# 2_matrix.net
KiCad netlist of a schematic drawn in Altium Designer
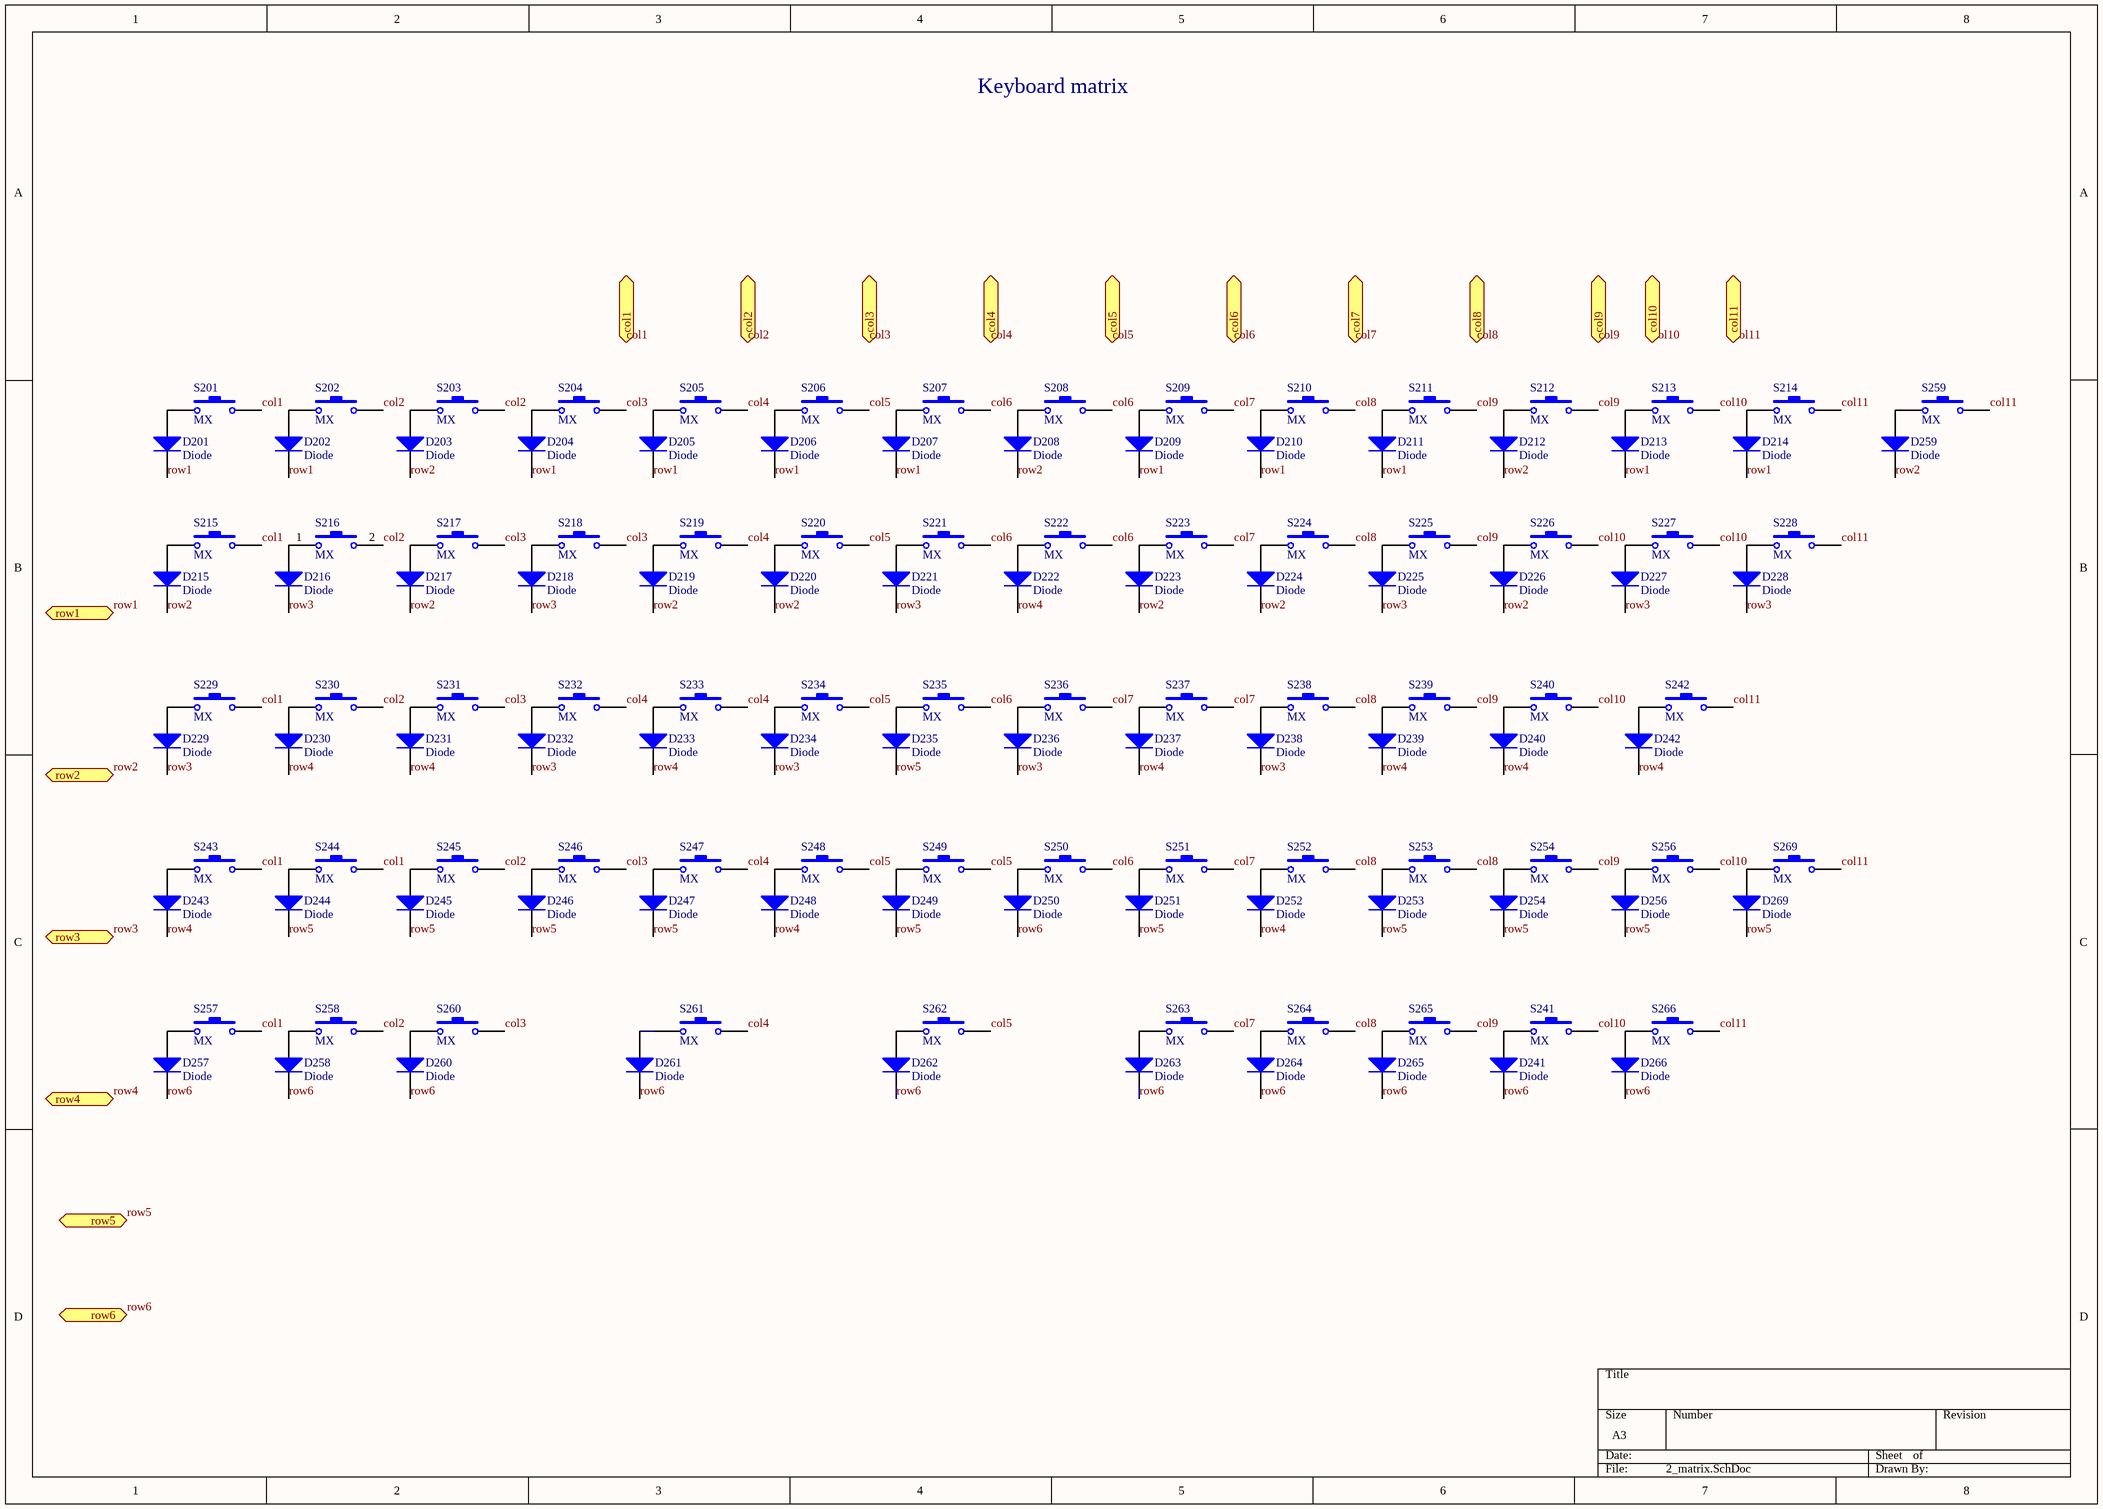
[diagram p0: 2_matrix.SchDoc]

(export (version "E")
  (design (tool "Eeschema 10.0.6"))
  (components
    (comp (ref "D201")
      (value "Diode")
      (footprint "D0603[1608]")
      (description "Default Diode")
      (fields (field (name "MFG") "Bourns Inc.") (field (name "MRF.PART") "CD4148WTP"))
      (libsource (lib "Miscellaneous Devices") (part "Diode"))
    )
    (comp (ref "D202")
      (value "Diode")
      (footprint "D0603[1608]")
      (description "Default Diode")
      (fields (field (name "MFG") "Bourns Inc.") (field (name "MRF.PART") "CD4148WTP"))
      (libsource (lib "Miscellaneous Devices") (part "Diode"))
    )
    (comp (ref "D203")
      (value "Diode")
      (footprint "D0603[1608]")
      (description "Default Diode")
      (fields (field (name "MFG") "Bourns Inc.") (field (name "MRF.PART") "CD4148WTP"))
      (libsource (lib "Miscellaneous Devices") (part "Diode"))
    )
    (comp (ref "D204")
      (value "Diode")
      (footprint "D0603[1608]")
      (description "Default Diode")
      (fields (field (name "MFG") "Bourns Inc.") (field (name "MRF.PART") "CD4148WTP"))
      (libsource (lib "Miscellaneous Devices") (part "Diode"))
    )
    (comp (ref "D205")
      (value "Diode")
      (footprint "D0603[1608]")
      (description "Default Diode")
      (fields (field (name "MFG") "Bourns Inc.") (field (name "MRF.PART") "CD4148WTP"))
      (libsource (lib "Miscellaneous Devices") (part "Diode"))
    )
    (comp (ref "D206")
      (value "Diode")
      (footprint "D0603[1608]")
      (description "Default Diode")
      (fields (field (name "MFG") "Bourns Inc.") (field (name "MRF.PART") "CD4148WTP"))
      (libsource (lib "Miscellaneous Devices") (part "Diode"))
    )
    (comp (ref "D207")
      (value "Diode")
      (footprint "D0603[1608]")
      (description "Default Diode")
      (fields (field (name "MFG") "Bourns Inc.") (field (name "MRF.PART") "CD4148WTP"))
      (libsource (lib "Miscellaneous Devices") (part "Diode"))
    )
    (comp (ref "D208")
      (value "Diode")
      (footprint "D0603[1608]")
      (description "Default Diode")
      (fields (field (name "MFG") "Bourns Inc.") (field (name "MRF.PART") "CD4148WTP"))
      (libsource (lib "Miscellaneous Devices") (part "Diode"))
    )
    (comp (ref "D209")
      (value "Diode")
      (footprint "D0603[1608]")
      (description "Default Diode")
      (fields (field (name "MFG") "Bourns Inc.") (field (name "MRF.PART") "CD4148WTP"))
      (libsource (lib "Miscellaneous Devices") (part "Diode"))
    )
    (comp (ref "D210")
      (value "Diode")
      (footprint "D0603[1608]")
      (description "Default Diode")
      (fields (field (name "MFG") "Bourns Inc.") (field (name "MRF.PART") "CD4148WTP"))
      (libsource (lib "Miscellaneous Devices") (part "Diode"))
    )
    (comp (ref "D211")
      (value "Diode")
      (footprint "D0603[1608]")
      (description "Default Diode")
      (fields (field (name "MFG") "Bourns Inc.") (field (name "MRF.PART") "CD4148WTP"))
      (libsource (lib "Miscellaneous Devices") (part "Diode"))
    )
    (comp (ref "D212")
      (value "Diode")
      (footprint "D0603[1608]")
      (description "Default Diode")
      (fields (field (name "MFG") "Bourns Inc.") (field (name "MRF.PART") "CD4148WTP"))
      (libsource (lib "Miscellaneous Devices") (part "Diode"))
    )
    (comp (ref "D213")
      (value "Diode")
      (footprint "D0603[1608]")
      (description "Default Diode")
      (fields (field (name "MFG") "Bourns Inc.") (field (name "MRF.PART") "CD4148WTP"))
      (libsource (lib "Miscellaneous Devices") (part "Diode"))
    )
    (comp (ref "D214")
      (value "Diode")
      (footprint "D0603[1608]")
      (description "Default Diode")
      (fields (field (name "MFG") "Bourns Inc.") (field (name "MRF.PART") "CD4148WTP"))
      (libsource (lib "Miscellaneous Devices") (part "Diode"))
    )
    (comp (ref "D215")
      (value "Diode")
      (footprint "D0603[1608]")
      (description "Default Diode")
      (fields (field (name "MFG") "Bourns Inc.") (field (name "MRF.PART") "CD4148WTP"))
      (libsource (lib "Miscellaneous Devices") (part "Diode"))
    )
    (comp (ref "D216")
      (value "Diode")
      (footprint "D0603[1608]")
      (description "Default Diode")
      (fields (field (name "MFG") "Bourns Inc.") (field (name "MRF.PART") "CD4148WTP"))
      (libsource (lib "Miscellaneous Devices") (part "Diode"))
    )
    (comp (ref "D217")
      (value "Diode")
      (footprint "D0603[1608]")
      (description "Default Diode")
      (fields (field (name "MFG") "Bourns Inc.") (field (name "MRF.PART") "CD4148WTP"))
      (libsource (lib "Miscellaneous Devices") (part "Diode"))
    )
    (comp (ref "D218")
      (value "Diode")
      (footprint "D0603[1608]")
      (description "Default Diode")
      (fields (field (name "MFG") "Bourns Inc.") (field (name "MRF.PART") "CD4148WTP"))
      (libsource (lib "Miscellaneous Devices") (part "Diode"))
    )
    (comp (ref "D219")
      (value "Diode")
      (footprint "D0603[1608]")
      (description "Default Diode")
      (fields (field (name "MFG") "Bourns Inc.") (field (name "MRF.PART") "CD4148WTP"))
      (libsource (lib "Miscellaneous Devices") (part "Diode"))
    )
    (comp (ref "D220")
      (value "Diode")
      (footprint "D0603[1608]")
      (description "Default Diode")
      (fields (field (name "MFG") "Bourns Inc.") (field (name "MRF.PART") "CD4148WTP"))
      (libsource (lib "Miscellaneous Devices") (part "Diode"))
    )
    (comp (ref "D221")
      (value "Diode")
      (footprint "D0603[1608]")
      (description "Default Diode")
      (fields (field (name "MFG") "Bourns Inc.") (field (name "MRF.PART") "CD4148WTP"))
      (libsource (lib "Miscellaneous Devices") (part "Diode"))
    )
    (comp (ref "D222")
      (value "Diode")
      (footprint "D0603[1608]")
      (description "Default Diode")
      (fields (field (name "MFG") "Bourns Inc.") (field (name "MRF.PART") "CD4148WTP"))
      (libsource (lib "Miscellaneous Devices") (part "Diode"))
    )
    (comp (ref "D223")
      (value "Diode")
      (footprint "D0603[1608]")
      (description "Default Diode")
      (fields (field (name "MFG") "Bourns Inc.") (field (name "MRF.PART") "CD4148WTP"))
      (libsource (lib "Miscellaneous Devices") (part "Diode"))
    )
    (comp (ref "D224")
      (value "Diode")
      (footprint "D0603[1608]")
      (description "Default Diode")
      (fields (field (name "MFG") "Bourns Inc.") (field (name "MRF.PART") "CD4148WTP"))
      (libsource (lib "Miscellaneous Devices") (part "Diode"))
    )
    (comp (ref "D225")
      (value "Diode")
      (footprint "D0603[1608]")
      (description "Default Diode")
      (fields (field (name "MFG") "Bourns Inc.") (field (name "MRF.PART") "CD4148WTP"))
      (libsource (lib "Miscellaneous Devices") (part "Diode"))
    )
    (comp (ref "D226")
      (value "Diode")
      (footprint "D0603[1608]")
      (description "Default Diode")
      (fields (field (name "MFG") "Bourns Inc.") (field (name "MRF.PART") "CD4148WTP"))
      (libsource (lib "Miscellaneous Devices") (part "Diode"))
    )
    (comp (ref "D227")
      (value "Diode")
      (footprint "D0603[1608]")
      (description "Default Diode")
      (fields (field (name "MFG") "Bourns Inc.") (field (name "MRF.PART") "CD4148WTP"))
      (libsource (lib "Miscellaneous Devices") (part "Diode"))
    )
    (comp (ref "D228")
      (value "Diode")
      (footprint "D0603[1608]")
      (description "Default Diode")
      (fields (field (name "MFG") "Bourns Inc.") (field (name "MRF.PART") "CD4148WTP"))
      (libsource (lib "Miscellaneous Devices") (part "Diode"))
    )
    (comp (ref "D229")
      (value "Diode")
      (footprint "D0603[1608]")
      (description "Default Diode")
      (fields (field (name "MFG") "Bourns Inc.") (field (name "MRF.PART") "CD4148WTP"))
      (libsource (lib "Miscellaneous Devices") (part "Diode"))
    )
    (comp (ref "D230")
      (value "Diode")
      (footprint "D0603[1608]")
      (description "Default Diode")
      (fields (field (name "MFG") "Bourns Inc.") (field (name "MRF.PART") "CD4148WTP"))
      (libsource (lib "Miscellaneous Devices") (part "Diode"))
    )
    (comp (ref "D231")
      (value "Diode")
      (footprint "D0603[1608]")
      (description "Default Diode")
      (fields (field (name "MFG") "Bourns Inc.") (field (name "MRF.PART") "CD4148WTP"))
      (libsource (lib "Miscellaneous Devices") (part "Diode"))
    )
    (comp (ref "D232")
      (value "Diode")
      (footprint "D0603[1608]")
      (description "Default Diode")
      (fields (field (name "MFG") "Bourns Inc.") (field (name "MRF.PART") "CD4148WTP"))
      (libsource (lib "Miscellaneous Devices") (part "Diode"))
    )
    (comp (ref "D233")
      (value "Diode")
      (footprint "D0603[1608]")
      (description "Default Diode")
      (fields (field (name "MFG") "Bourns Inc.") (field (name "MRF.PART") "CD4148WTP"))
      (libsource (lib "Miscellaneous Devices") (part "Diode"))
    )
    (comp (ref "D234")
      (value "Diode")
      (footprint "D0603[1608]")
      (description "Default Diode")
      (fields (field (name "MFG") "Bourns Inc.") (field (name "MRF.PART") "CD4148WTP"))
      (libsource (lib "Miscellaneous Devices") (part "Diode"))
    )
    (comp (ref "D235")
      (value "Diode")
      (footprint "D0603[1608]")
      (description "Default Diode")
      (fields (field (name "MFG") "Bourns Inc.") (field (name "MRF.PART") "CD4148WTP"))
      (libsource (lib "Miscellaneous Devices") (part "Diode"))
    )
    (comp (ref "D236")
      (value "Diode")
      (footprint "D0603[1608]")
      (description "Default Diode")
      (fields (field (name "MFG") "Bourns Inc.") (field (name "MRF.PART") "CD4148WTP"))
      (libsource (lib "Miscellaneous Devices") (part "Diode"))
    )
    (comp (ref "D237")
      (value "Diode")
      (footprint "D0603[1608]")
      (description "Default Diode")
      (fields (field (name "MFG") "Bourns Inc.") (field (name "MRF.PART") "CD4148WTP"))
      (libsource (lib "Miscellaneous Devices") (part "Diode"))
    )
    (comp (ref "D238")
      (value "Diode")
      (footprint "D0603[1608]")
      (description "Default Diode")
      (fields (field (name "MFG") "Bourns Inc.") (field (name "MRF.PART") "CD4148WTP"))
      (libsource (lib "Miscellaneous Devices") (part "Diode"))
    )
    (comp (ref "D239")
      (value "Diode")
      (footprint "D0603[1608]")
      (description "Default Diode")
      (fields (field (name "MFG") "Bourns Inc.") (field (name "MRF.PART") "CD4148WTP"))
      (libsource (lib "Miscellaneous Devices") (part "Diode"))
    )
    (comp (ref "D240")
      (value "Diode")
      (footprint "D0603[1608]")
      (description "Default Diode")
      (fields (field (name "MFG") "Bourns Inc.") (field (name "MRF.PART") "CD4148WTP"))
      (libsource (lib "Miscellaneous Devices") (part "Diode"))
    )
    (comp (ref "D241")
      (value "Diode")
      (footprint "D0603[1608]")
      (description "Default Diode")
      (fields (field (name "MFG") "Bourns Inc.") (field (name "MRF.PART") "CD4148WTP"))
      (libsource (lib "Miscellaneous Devices") (part "Diode"))
    )
    (comp (ref "D242")
      (value "Diode")
      (footprint "D0603[1608]")
      (description "Default Diode")
      (fields (field (name "MFG") "Bourns Inc.") (field (name "MRF.PART") "CD4148WTP"))
      (libsource (lib "Miscellaneous Devices") (part "Diode"))
    )
    (comp (ref "D243")
      (value "Diode")
      (footprint "D0603[1608]")
      (description "Default Diode")
      (fields (field (name "MFG") "Bourns Inc.") (field (name "MRF.PART") "CD4148WTP"))
      (libsource (lib "Miscellaneous Devices") (part "Diode"))
    )
    (comp (ref "D244")
      (value "Diode")
      (footprint "D0603[1608]")
      (description "Default Diode")
      (fields (field (name "MFG") "Bourns Inc.") (field (name "MRF.PART") "CD4148WTP"))
      (libsource (lib "Miscellaneous Devices") (part "Diode"))
    )
    (comp (ref "D245")
      (value "Diode")
      (footprint "D0603[1608]")
      (description "Default Diode")
      (fields (field (name "MFG") "Bourns Inc.") (field (name "MRF.PART") "CD4148WTP"))
      (libsource (lib "Miscellaneous Devices") (part "Diode"))
    )
    (comp (ref "D246")
      (value "Diode")
      (footprint "D0603[1608]")
      (description "Default Diode")
      (fields (field (name "MFG") "Bourns Inc.") (field (name "MRF.PART") "CD4148WTP"))
      (libsource (lib "Miscellaneous Devices") (part "Diode"))
    )
    (comp (ref "D247")
      (value "Diode")
      (footprint "D0603[1608]")
      (description "Default Diode")
      (fields (field (name "MFG") "Bourns Inc.") (field (name "MRF.PART") "CD4148WTP"))
      (libsource (lib "Miscellaneous Devices") (part "Diode"))
    )
    (comp (ref "D248")
      (value "Diode")
      (footprint "D0603[1608]")
      (description "Default Diode")
      (fields (field (name "MFG") "Bourns Inc.") (field (name "MRF.PART") "CD4148WTP"))
      (libsource (lib "Miscellaneous Devices") (part "Diode"))
    )
    (comp (ref "D249")
      (value "Diode")
      (footprint "D0603[1608]")
      (description "Default Diode")
      (fields (field (name "MFG") "Bourns Inc.") (field (name "MRF.PART") "CD4148WTP"))
      (libsource (lib "Miscellaneous Devices") (part "Diode"))
    )
    (comp (ref "D250")
      (value "Diode")
      (footprint "D0603[1608]")
      (description "Default Diode")
      (fields (field (name "MFG") "Bourns Inc.") (field (name "MRF.PART") "CD4148WTP"))
      (libsource (lib "Miscellaneous Devices") (part "Diode"))
    )
    (comp (ref "D251")
      (value "Diode")
      (footprint "D0603[1608]")
      (description "Default Diode")
      (fields (field (name "MFG") "Bourns Inc.") (field (name "MRF.PART") "CD4148WTP"))
      (libsource (lib "Miscellaneous Devices") (part "Diode"))
    )
    (comp (ref "D252")
      (value "Diode")
      (footprint "D0603[1608]")
      (description "Default Diode")
      (fields (field (name "MFG") "Bourns Inc.") (field (name "MRF.PART") "CD4148WTP"))
      (libsource (lib "Miscellaneous Devices") (part "Diode"))
    )
    (comp (ref "D253")
      (value "Diode")
      (footprint "D0603[1608]")
      (description "Default Diode")
      (fields (field (name "MFG") "Bourns Inc.") (field (name "MRF.PART") "CD4148WTP"))
      (libsource (lib "Miscellaneous Devices") (part "Diode"))
    )
    (comp (ref "D254")
      (value "Diode")
      (footprint "D0603[1608]")
      (description "Default Diode")
      (fields (field (name "MFG") "Bourns Inc.") (field (name "MRF.PART") "CD4148WTP"))
      (libsource (lib "Miscellaneous Devices") (part "Diode"))
    )
    (comp (ref "D256")
      (value "Diode")
      (footprint "D0603[1608]")
      (description "Default Diode")
      (fields (field (name "MFG") "Bourns Inc.") (field (name "MRF.PART") "CD4148WTP"))
      (libsource (lib "Miscellaneous Devices") (part "Diode"))
    )
    (comp (ref "D257")
      (value "Diode")
      (footprint "D0603[1608]")
      (description "Default Diode")
      (fields (field (name "MFG") "Bourns Inc.") (field (name "MRF.PART") "CD4148WTP"))
      (libsource (lib "Miscellaneous Devices") (part "Diode"))
    )
    (comp (ref "D258")
      (value "Diode")
      (footprint "D0603[1608]")
      (description "Default Diode")
      (fields (field (name "MFG") "Bourns Inc.") (field (name "MRF.PART") "CD4148WTP"))
      (libsource (lib "Miscellaneous Devices") (part "Diode"))
    )
    (comp (ref "D259")
      (value "Diode")
      (footprint "D0603[1608]")
      (description "Default Diode")
      (fields (field (name "MFG") "Bourns Inc.") (field (name "MRF.PART") "CD4148WTP"))
      (libsource (lib "Miscellaneous Devices") (part "Diode"))
    )
    (comp (ref "D260")
      (value "Diode")
      (footprint "D0603[1608]")
      (description "Default Diode")
      (fields (field (name "MFG") "Bourns Inc.") (field (name "MRF.PART") "CD4148WTP"))
      (libsource (lib "Miscellaneous Devices") (part "Diode"))
    )
    (comp (ref "D261")
      (value "Diode")
      (footprint "D0603[1608]")
      (description "Default Diode")
      (fields (field (name "MFG") "Bourns Inc.") (field (name "MRF.PART") "CD4148WTP"))
      (libsource (lib "Miscellaneous Devices") (part "Diode"))
    )
    (comp (ref "D262")
      (value "Diode")
      (footprint "D0603[1608]")
      (description "Default Diode")
      (fields (field (name "MFG") "Bourns Inc.") (field (name "MRF.PART") "CD4148WTP"))
      (libsource (lib "Miscellaneous Devices") (part "Diode"))
    )
    (comp (ref "D263")
      (value "Diode")
      (footprint "D0603[1608]")
      (description "Default Diode")
      (fields (field (name "MFG") "Bourns Inc.") (field (name "MRF.PART") "CD4148WTP"))
      (libsource (lib "Miscellaneous Devices") (part "Diode"))
    )
    (comp (ref "D264")
      (value "Diode")
      (footprint "D0603[1608]")
      (description "Default Diode")
      (fields (field (name "MFG") "Bourns Inc.") (field (name "MRF.PART") "CD4148WTP"))
      (libsource (lib "Miscellaneous Devices") (part "Diode"))
    )
    (comp (ref "D265")
      (value "Diode")
      (footprint "D0603[1608]")
      (description "Default Diode")
      (fields (field (name "MFG") "Bourns Inc.") (field (name "MRF.PART") "CD4148WTP"))
      (libsource (lib "Miscellaneous Devices") (part "Diode"))
    )
    (comp (ref "D266")
      (value "Diode")
      (footprint "D0603[1608]")
      (description "Default Diode")
      (fields (field (name "MFG") "Bourns Inc.") (field (name "MRF.PART") "CD4148WTP"))
      (libsource (lib "Miscellaneous Devices") (part "Diode"))
    )
    (comp (ref "D269")
      (value "Diode")
      (footprint "D0603[1608]")
      (description "Default Diode")
      (fields (field (name "MFG") "Bourns Inc.") (field (name "MRF.PART") "CD4148WTP"))
      (libsource (lib "Miscellaneous Devices") (part "Diode"))
    )
    (comp (ref "S201")
      (value "MX")
      (footprint "MXHS-switch")
      (description "Switch")
      (libsource (lib "Miscellaneous Devices") (part "SW-PB"))
    )
    (comp (ref "S202")
      (value "MX")
      (footprint "MXHS-switch")
      (description "Switch")
      (libsource (lib "Miscellaneous Devices") (part "SW-PB"))
    )
    (comp (ref "S203")
      (value "MX")
      (footprint "MXHS-switch")
      (description "Switch")
      (libsource (lib "Miscellaneous Devices") (part "SW-PB"))
    )
    (comp (ref "S204")
      (value "MX")
      (footprint "MXHS-switch")
      (description "Switch")
      (libsource (lib "Miscellaneous Devices") (part "SW-PB"))
    )
    (comp (ref "S205")
      (value "MX")
      (footprint "MXHS-switch")
      (description "Switch")
      (libsource (lib "Miscellaneous Devices") (part "SW-PB"))
    )
    (comp (ref "S206")
      (value "MX")
      (footprint "MXHS-switch")
      (description "Switch")
      (libsource (lib "Miscellaneous Devices") (part "SW-PB"))
    )
    (comp (ref "S207")
      (value "MX")
      (footprint "MXHS-switch_Switched_Pol")
      (description "Switch")
      (libsource (lib "Miscellaneous Devices") (part "SW-PB"))
    )
    (comp (ref "S208")
      (value "MX")
      (footprint "MXHS-switch")
      (description "Switch")
      (libsource (lib "Miscellaneous Devices") (part "SW-PB"))
    )
    (comp (ref "S209")
      (value "MX")
      (footprint "MXHS-switch")
      (description "Switch")
      (libsource (lib "Miscellaneous Devices") (part "SW-PB"))
    )
    (comp (ref "S210")
      (value "MX")
      (footprint "MXHS-switch")
      (description "Switch")
      (libsource (lib "Miscellaneous Devices") (part "SW-PB"))
    )
    (comp (ref "S211")
      (value "MX")
      (footprint "MXHS-switch_Switched_Pol")
      (description "Switch")
      (libsource (lib "Miscellaneous Devices") (part "SW-PB"))
    )
    (comp (ref "S212")
      (value "MX")
      (footprint "MXHS-switch")
      (description "Switch")
      (libsource (lib "Miscellaneous Devices") (part "SW-PB"))
    )
    (comp (ref "S213")
      (value "MX")
      (footprint "MXHS-switch")
      (description "Switch")
      (libsource (lib "Miscellaneous Devices") (part "SW-PB"))
    )
    (comp (ref "S214")
      (value "MX")
      (footprint "MXHS-switch")
      (description "Switch")
      (libsource (lib "Miscellaneous Devices") (part "SW-PB"))
    )
    (comp (ref "S215")
      (value "MX")
      (footprint "MXHS-SWITCH - 1.5U")
      (description "TAB")
      (libsource (lib "Miscellaneous Devices") (part "SW-PB"))
    )
    (comp (ref "S216")
      (value "MX")
      (footprint "MXHS-switch")
      (description "Switch")
      (libsource (lib "") (part "SW-PB_1"))
    )
    (comp (ref "S217")
      (value "MX")
      (footprint "MXHS-switch")
      (description "Switch")
      (libsource (lib "Miscellaneous Devices") (part "SW-PB"))
    )
    (comp (ref "S218")
      (value "MX")
      (footprint "MXHS-switch")
      (description "Switch")
      (libsource (lib "Miscellaneous Devices") (part "SW-PB"))
    )
    (comp (ref "S219")
      (value "MX")
      (footprint "MXHS-switch")
      (description "Switch")
      (libsource (lib "Miscellaneous Devices") (part "SW-PB"))
    )
    (comp (ref "S220")
      (value "MX")
      (footprint "MXHS-switch")
      (description "Switch")
      (libsource (lib "Miscellaneous Devices") (part "SW-PB"))
    )
    (comp (ref "S221")
      (value "MX")
      (footprint "MXHS-switch")
      (description "Switch")
      (libsource (lib "Miscellaneous Devices") (part "SW-PB"))
    )
    (comp (ref "S222")
      (value "MX")
      (footprint "MXHS-switch")
      (description "Switch")
      (libsource (lib "Miscellaneous Devices") (part "SW-PB"))
    )
    (comp (ref "S223")
      (value "MX")
      (footprint "MXHS-switch")
      (description "Switch")
      (libsource (lib "Miscellaneous Devices") (part "SW-PB"))
    )
    (comp (ref "S224")
      (value "MX")
      (footprint "MXHS-switch")
      (description "Switch")
      (libsource (lib "Miscellaneous Devices") (part "SW-PB"))
    )
    (comp (ref "S225")
      (value "MX")
      (footprint "MXHS-switch")
      (description "Switch")
      (libsource (lib "Miscellaneous Devices") (part "SW-PB"))
    )
    (comp (ref "S226")
      (value "MX")
      (footprint "MXHS-switch_Switched_Pol")
      (description "Switch")
      (libsource (lib "Miscellaneous Devices") (part "SW-PB"))
    )
    (comp (ref "S227")
      (value "MX")
      (footprint "MXHS-switch")
      (description "Switch")
      (libsource (lib "Miscellaneous Devices") (part "SW-PB"))
    )
    (comp (ref "S228")
      (value "MX")
      (footprint "MXHS-SWITCH - PIPE_ISO_ENTER")
      (description "Switch")
      (libsource (lib "Miscellaneous Devices") (part "SW-PB"))
    )
    (comp (ref "S229")
      (value "MX")
      (footprint "MXHS-SWITCH - CAPS_STEPPED_DUAL")
      (description "Switch")
      (libsource (lib "Miscellaneous Devices") (part "SW-PB"))
    )
    (comp (ref "S230")
      (value "MX")
      (footprint "MXHS-switch")
      (description "Switch")
      (libsource (lib "Miscellaneous Devices") (part "SW-PB"))
    )
    (comp (ref "S231")
      (value "MX")
      (footprint "MXHS-switch")
      (description "Switch")
      (libsource (lib "Miscellaneous Devices") (part "SW-PB"))
    )
    (comp (ref "S232")
      (value "MX")
      (footprint "MXHS-switch_Switched_Pol")
      (description "Switch")
      (libsource (lib "Miscellaneous Devices") (part "SW-PB"))
    )
    (comp (ref "S233")
      (value "MX")
      (footprint "MXHS-switch")
      (description "Switch")
      (libsource (lib "Miscellaneous Devices") (part "SW-PB"))
    )
    (comp (ref "S234")
      (value "MX")
      (footprint "MXHS-switch")
      (description "Switch")
      (libsource (lib "Miscellaneous Devices") (part "SW-PB"))
    )
    (comp (ref "S235")
      (value "MX")
      (footprint "MXHS-switch")
      (description "Switch")
      (libsource (lib "Miscellaneous Devices") (part "SW-PB"))
    )
    (comp (ref "S236")
      (value "MX")
      (footprint "MXHS-switch_Switched_Pol")
      (description "Switch")
      (libsource (lib "Miscellaneous Devices") (part "SW-PB"))
    )
    (comp (ref "S237")
      (value "MX")
      (footprint "MXHS-switch")
      (description "Switch")
      (libsource (lib "Miscellaneous Devices") (part "SW-PB"))
    )
    (comp (ref "S238")
      (value "MX")
      (footprint "MXHS-switch")
      (description "Switch")
      (libsource (lib "Miscellaneous Devices") (part "SW-PB"))
    )
    (comp (ref "S239")
      (value "MX")
      (footprint "MXHS-switch")
      (description "Switch")
      (libsource (lib "Miscellaneous Devices") (part "SW-PB"))
    )
    (comp (ref "S240")
      (value "MX")
      (footprint "MXHS-switch")
      (description "Switch")
      (libsource (lib "Miscellaneous Devices") (part "SW-PB"))
    )
    (comp (ref "S241")
      (value "MX")
      (footprint "MXHS-SWITCH - R_WIN")
      (description "Switch")
      (libsource (lib "Miscellaneous Devices") (part "SW-PB"))
    )
    (comp (ref "S242")
      (value "MX")
      (footprint "MXHS-SWITCH - ENTER_ANSI_ISO_KEY_V2")
      (description "Switch")
      (libsource (lib "Miscellaneous Devices") (part "SW-PB"))
    )
    (comp (ref "S243")
      (value "MX")
      (footprint "MXHS-switch - Left shift")
      (description "Switch")
      (libsource (lib "Miscellaneous Devices") (part "SW-PB"))
    )
    (comp (ref "S244")
      (value "MX")
      (footprint "MXHS-switch")
      (description "Switch")
      (libsource (lib "Miscellaneous Devices") (part "SW-PB"))
    )
    (comp (ref "S245")
      (value "MX")
      (footprint "MXHS-switch")
      (description "Switch")
      (libsource (lib "Miscellaneous Devices") (part "SW-PB"))
    )
    (comp (ref "S246")
      (value "MX")
      (footprint "MXHS-switch")
      (description "Switch")
      (libsource (lib "Miscellaneous Devices") (part "SW-PB"))
    )
    (comp (ref "S247")
      (value "MX")
      (footprint "MXHS-switch_Switched_Pol")
      (description "Switch")
      (libsource (lib "Miscellaneous Devices") (part "SW-PB"))
    )
    (comp (ref "S248")
      (value "MX")
      (footprint "MXHS-switch_Switched_Pol")
      (description "Switch")
      (libsource (lib "Miscellaneous Devices") (part "SW-PB"))
    )
    (comp (ref "S249")
      (value "MX")
      (footprint "MXHS-switch")
      (description "Switch")
      (libsource (lib "Miscellaneous Devices") (part "SW-PB"))
    )
    (comp (ref "S250")
      (value "MX")
      (footprint "MXHS-switch")
      (description "Switch")
      (libsource (lib "Miscellaneous Devices") (part "SW-PB"))
    )
    (comp (ref "S251")
      (value "MX")
      (footprint "MXHS-switch_Switched_Pol")
      (description "Switch")
      (libsource (lib "Miscellaneous Devices") (part "SW-PB"))
    )
    (comp (ref "S252")
      (value "MX")
      (footprint "MXHS-switch_Switched_Pol")
      (description "Switch")
      (libsource (lib "Miscellaneous Devices") (part "SW-PB"))
    )
    (comp (ref "S253")
      (value "MX")
      (footprint "MXHS-switch")
      (description "Switch")
      (libsource (lib "Miscellaneous Devices") (part "SW-PB"))
    )
    (comp (ref "S254")
      (value "MX")
      (footprint "MXHS-switch")
      (description "Switch")
      (libsource (lib "Miscellaneous Devices") (part "SW-PB"))
    )
    (comp (ref "S256")
      (value "MX")
      (footprint "MXHS-switch - right shift")
      (description "Switch")
      (libsource (lib "Miscellaneous Devices") (part "SW-PB"))
    )
    (comp (ref "S257")
      (value "MX")
      (footprint "MXHS-switch - L_CTRL")
      (description "Switch")
      (libsource (lib "Miscellaneous Devices") (part "SW-PB"))
    )
    (comp (ref "S258")
      (value "MX")
      (footprint "MXHS-switch - L_WIN")
      (description "Switch")
      (libsource (lib "Miscellaneous Devices") (part "SW-PB"))
    )
    (comp (ref "S259")
      (value "MX")
      (footprint "MXHS-switch - backspace")
      (description "Switch")
      (libsource (lib "Miscellaneous Devices") (part "SW-PB"))
    )
    (comp (ref "S260")
      (value "MX")
      (footprint "MXHS-switch - L_alt")
      (description "Switch")
      (libsource (lib "Miscellaneous Devices") (part "SW-PB"))
    )
    (comp (ref "S261")
      (value "MX")
      (footprint "MXHS-SWITCH - L SPLIT SPACE")
      (description "Switch")
      (libsource (lib "Miscellaneous Devices") (part "SW-PB"))
    )
    (comp (ref "S262")
      (value "MX")
      (footprint "MXHS-switch - Space_V2")
      (description "Switch")
      (libsource (lib "Miscellaneous Devices") (part "SW-PB"))
    )
    (comp (ref "S263")
      (value "MX")
      (footprint "MXHS-SWITCH - R SPLIT SPACE")
      (description "Switch")
      (libsource (lib "Miscellaneous Devices") (part "SW-PB"))
    )
    (comp (ref "S264")
      (value "MX")
      (footprint "MXHS-switch")
      (description "Switch")
      (libsource (lib "Miscellaneous Devices") (part "SW-PB"))
    )
    (comp (ref "S265")
      (value "MX")
      (footprint "MXHS-SWITCH - R_ALT_V2")
      (description "Switch")
      (libsource (lib "Miscellaneous Devices") (part "SW-PB"))
    )
    (comp (ref "S266")
      (value "MX")
      (footprint "MXHS-SWITCH - R_CTRL")
      (description "Switch")
      (libsource (lib "Miscellaneous Devices") (part "SW-PB"))
    )
    (comp (ref "S269")
      (value "MX")
      (footprint "MXHS-switch")
      (description "Switch")
      (libsource (lib "Miscellaneous Devices") (part "SW-PB"))
    )
  )
  (nets
    (net (code "1") (name "/col1") (class "Default")
      (node (ref "S201") (pin "2") (pinfunction "2_2") (pintype "passive"))
      (node (ref "S215") (pin "2") (pinfunction "2_2") (pintype "passive"))
      (node (ref "S229") (pin "2") (pinfunction "2_2") (pintype "passive"))
      (node (ref "S243") (pin "2") (pinfunction "2_2") (pintype "passive"))
      (node (ref "S244") (pin "2") (pinfunction "2_2") (pintype "passive"))
      (node (ref "S257") (pin "2") (pinfunction "2_2") (pintype "passive"))
    )
    (net (code "2") (name "/col2") (class "Default")
      (node (ref "S202") (pin "2") (pinfunction "2_2") (pintype "passive"))
      (node (ref "S203") (pin "2") (pinfunction "2_2") (pintype "passive"))
      (node (ref "S216") (pin "2") (pinfunction "2_2") (pintype "passive"))
      (node (ref "S230") (pin "2") (pinfunction "2_2") (pintype "passive"))
      (node (ref "S245") (pin "2") (pinfunction "2_2") (pintype "passive"))
      (node (ref "S258") (pin "2") (pinfunction "2_2") (pintype "passive"))
    )
    (net (code "3") (name "/col3") (class "Default")
      (node (ref "S204") (pin "2") (pinfunction "2_2") (pintype "passive"))
      (node (ref "S217") (pin "2") (pinfunction "2_2") (pintype "passive"))
      (node (ref "S218") (pin "2") (pinfunction "2_2") (pintype "passive"))
      (node (ref "S231") (pin "2") (pinfunction "2_2") (pintype "passive"))
      (node (ref "S246") (pin "2") (pinfunction "2_2") (pintype "passive"))
      (node (ref "S260") (pin "2") (pinfunction "2_2") (pintype "passive"))
    )
    (net (code "4") (name "/col4") (class "Default")
      (node (ref "S205") (pin "2") (pinfunction "2_2") (pintype "passive"))
      (node (ref "S219") (pin "2") (pinfunction "2_2") (pintype "passive"))
      (node (ref "S232") (pin "2") (pinfunction "2_2") (pintype "passive"))
      (node (ref "S233") (pin "2") (pinfunction "2_2") (pintype "passive"))
      (node (ref "S247") (pin "2") (pinfunction "2_2") (pintype "passive"))
      (node (ref "S261") (pin "2") (pinfunction "2_2") (pintype "passive"))
    )
    (net (code "5") (name "/col5") (class "Default")
      (node (ref "S206") (pin "2") (pinfunction "2_2") (pintype "passive"))
      (node (ref "S220") (pin "2") (pinfunction "2_2") (pintype "passive"))
      (node (ref "S234") (pin "2") (pinfunction "2_2") (pintype "passive"))
      (node (ref "S248") (pin "2") (pinfunction "2_2") (pintype "passive"))
      (node (ref "S249") (pin "2") (pinfunction "2_2") (pintype "passive"))
      (node (ref "S262") (pin "2") (pinfunction "2_2") (pintype "passive"))
    )
    (net (code "6") (name "/col6") (class "Default")
      (node (ref "S207") (pin "2") (pinfunction "2_2") (pintype "passive"))
      (node (ref "S208") (pin "2") (pinfunction "2_2") (pintype "passive"))
      (node (ref "S221") (pin "2") (pinfunction "2_2") (pintype "passive"))
      (node (ref "S222") (pin "2") (pinfunction "2_2") (pintype "passive"))
      (node (ref "S235") (pin "2") (pinfunction "2_2") (pintype "passive"))
      (node (ref "S250") (pin "2") (pinfunction "2_2") (pintype "passive"))
    )
    (net (code "7") (name "/col7") (class "Default")
      (node (ref "S209") (pin "2") (pinfunction "2_2") (pintype "passive"))
      (node (ref "S223") (pin "2") (pinfunction "2_2") (pintype "passive"))
      (node (ref "S236") (pin "2") (pinfunction "2_2") (pintype "passive"))
      (node (ref "S237") (pin "2") (pinfunction "2_2") (pintype "passive"))
      (node (ref "S251") (pin "2") (pinfunction "2_2") (pintype "passive"))
      (node (ref "S263") (pin "2") (pinfunction "2_2") (pintype "passive"))
    )
    (net (code "8") (name "/col8") (class "Default")
      (node (ref "S210") (pin "2") (pinfunction "2_2") (pintype "passive"))
      (node (ref "S224") (pin "2") (pinfunction "2_2") (pintype "passive"))
      (node (ref "S238") (pin "2") (pinfunction "2_2") (pintype "passive"))
      (node (ref "S252") (pin "2") (pinfunction "2_2") (pintype "passive"))
      (node (ref "S253") (pin "2") (pinfunction "2_2") (pintype "passive"))
      (node (ref "S264") (pin "2") (pinfunction "2_2") (pintype "passive"))
    )
    (net (code "9") (name "/col9") (class "Default")
      (node (ref "S211") (pin "2") (pinfunction "2_2") (pintype "passive"))
      (node (ref "S212") (pin "2") (pinfunction "2_2") (pintype "passive"))
      (node (ref "S225") (pin "2") (pinfunction "2_2") (pintype "passive"))
      (node (ref "S239") (pin "2") (pinfunction "2_2") (pintype "passive"))
      (node (ref "S254") (pin "2") (pinfunction "2_2") (pintype "passive"))
      (node (ref "S265") (pin "2") (pinfunction "2_2") (pintype "passive"))
    )
    (net (code "10") (name "/col10") (class "Default")
      (node (ref "S213") (pin "2") (pinfunction "2_2") (pintype "passive"))
      (node (ref "S226") (pin "2") (pinfunction "2_2") (pintype "passive"))
      (node (ref "S227") (pin "2") (pinfunction "2_2") (pintype "passive"))
      (node (ref "S240") (pin "2") (pinfunction "2_2") (pintype "passive"))
      (node (ref "S241") (pin "2") (pinfunction "2_2") (pintype "passive"))
      (node (ref "S256") (pin "2") (pinfunction "2_2") (pintype "passive"))
    )
    (net (code "11") (name "/col11") (class "Default")
      (node (ref "S214") (pin "2") (pinfunction "2_2") (pintype "passive"))
      (node (ref "S228") (pin "2") (pinfunction "2_2") (pintype "passive"))
      (node (ref "S242") (pin "2") (pinfunction "2_2") (pintype "passive"))
      (node (ref "S259") (pin "2") (pinfunction "2_2") (pintype "passive"))
      (node (ref "S266") (pin "2") (pinfunction "2_2") (pintype "passive"))
      (node (ref "S269") (pin "2") (pinfunction "2_2") (pintype "passive"))
    )
    (net (code "12") (name "/row1") (class "Default")
      (node (ref "D201") (pin "2") (pinfunction "K_2") (pintype "passive"))
      (node (ref "D202") (pin "2") (pinfunction "K_2") (pintype "passive"))
      (node (ref "D204") (pin "2") (pinfunction "K_2") (pintype "passive"))
      (node (ref "D205") (pin "2") (pinfunction "K_2") (pintype "passive"))
      (node (ref "D206") (pin "2") (pinfunction "K_2") (pintype "passive"))
      (node (ref "D207") (pin "2") (pinfunction "K_2") (pintype "passive"))
      (node (ref "D209") (pin "2") (pinfunction "K_2") (pintype "passive"))
      (node (ref "D210") (pin "2") (pinfunction "K_2") (pintype "passive"))
      (node (ref "D211") (pin "2") (pinfunction "K_2") (pintype "passive"))
      (node (ref "D213") (pin "2") (pinfunction "K_2") (pintype "passive"))
      (node (ref "D214") (pin "2") (pinfunction "K_2") (pintype "passive"))
    )
    (net (code "13") (name "/row2") (class "Default")
      (node (ref "D203") (pin "2") (pinfunction "K_2") (pintype "passive"))
      (node (ref "D208") (pin "2") (pinfunction "K_2") (pintype "passive"))
      (node (ref "D212") (pin "2") (pinfunction "K_2") (pintype "passive"))
      (node (ref "D215") (pin "2") (pinfunction "K_2") (pintype "passive"))
      (node (ref "D217") (pin "2") (pinfunction "K_2") (pintype "passive"))
      (node (ref "D219") (pin "2") (pinfunction "K_2") (pintype "passive"))
      (node (ref "D220") (pin "2") (pinfunction "K_2") (pintype "passive"))
      (node (ref "D223") (pin "2") (pinfunction "K_2") (pintype "passive"))
      (node (ref "D224") (pin "2") (pinfunction "K_2") (pintype "passive"))
      (node (ref "D226") (pin "2") (pinfunction "K_2") (pintype "passive"))
      (node (ref "D259") (pin "2") (pinfunction "K_2") (pintype "passive"))
    )
    (net (code "14") (name "/row3") (class "Default")
      (node (ref "D216") (pin "2") (pinfunction "K_2") (pintype "passive"))
      (node (ref "D218") (pin "2") (pinfunction "K_2") (pintype "passive"))
      (node (ref "D221") (pin "2") (pinfunction "K_2") (pintype "passive"))
      (node (ref "D225") (pin "2") (pinfunction "K_2") (pintype "passive"))
      (node (ref "D227") (pin "2") (pinfunction "K_2") (pintype "passive"))
      (node (ref "D228") (pin "2") (pinfunction "K_2") (pintype "passive"))
      (node (ref "D229") (pin "2") (pinfunction "K_2") (pintype "passive"))
      (node (ref "D232") (pin "2") (pinfunction "K_2") (pintype "passive"))
      (node (ref "D234") (pin "2") (pinfunction "K_2") (pintype "passive"))
      (node (ref "D236") (pin "2") (pinfunction "K_2") (pintype "passive"))
      (node (ref "D238") (pin "2") (pinfunction "K_2") (pintype "passive"))
    )
    (net (code "15") (name "/row4") (class "Default")
      (node (ref "D222") (pin "2") (pinfunction "K_2") (pintype "passive"))
      (node (ref "D230") (pin "2") (pinfunction "K_2") (pintype "passive"))
      (node (ref "D231") (pin "2") (pinfunction "K_2") (pintype "passive"))
      (node (ref "D233") (pin "2") (pinfunction "K_2") (pintype "passive"))
      (node (ref "D237") (pin "2") (pinfunction "K_2") (pintype "passive"))
      (node (ref "D239") (pin "2") (pinfunction "K_2") (pintype "passive"))
      (node (ref "D240") (pin "2") (pinfunction "K_2") (pintype "passive"))
      (node (ref "D242") (pin "2") (pinfunction "K_2") (pintype "passive"))
      (node (ref "D243") (pin "2") (pinfunction "K_2") (pintype "passive"))
      (node (ref "D248") (pin "2") (pinfunction "K_2") (pintype "passive"))
      (node (ref "D252") (pin "2") (pinfunction "K_2") (pintype "passive"))
    )
    (net (code "16") (name "/row5") (class "Default")
      (node (ref "D235") (pin "2") (pinfunction "K_2") (pintype "passive"))
      (node (ref "D244") (pin "2") (pinfunction "K_2") (pintype "passive"))
      (node (ref "D245") (pin "2") (pinfunction "K_2") (pintype "passive"))
      (node (ref "D246") (pin "2") (pinfunction "K_2") (pintype "passive"))
      (node (ref "D247") (pin "2") (pinfunction "K_2") (pintype "passive"))
      (node (ref "D249") (pin "2") (pinfunction "K_2") (pintype "passive"))
      (node (ref "D251") (pin "2") (pinfunction "K_2") (pintype "passive"))
      (node (ref "D253") (pin "2") (pinfunction "K_2") (pintype "passive"))
      (node (ref "D254") (pin "2") (pinfunction "K_2") (pintype "passive"))
      (node (ref "D256") (pin "2") (pinfunction "K_2") (pintype "passive"))
      (node (ref "D269") (pin "2") (pinfunction "K_2") (pintype "passive"))
    )
    (net (code "17") (name "/row6") (class "Default")
      (node (ref "D241") (pin "2") (pinfunction "K_2") (pintype "passive"))
      (node (ref "D250") (pin "2") (pinfunction "K_2") (pintype "passive"))
      (node (ref "D257") (pin "2") (pinfunction "K_2") (pintype "passive"))
      (node (ref "D258") (pin "2") (pinfunction "K_2") (pintype "passive"))
      (node (ref "D260") (pin "2") (pinfunction "K_2") (pintype "passive"))
      (node (ref "D261") (pin "2") (pinfunction "K_2") (pintype "passive"))
      (node (ref "D262") (pin "2") (pinfunction "K_2") (pintype "passive"))
      (node (ref "D263") (pin "2") (pinfunction "K_2") (pintype "passive"))
      (node (ref "D264") (pin "2") (pinfunction "K_2") (pintype "passive"))
      (node (ref "D265") (pin "2") (pinfunction "K_2") (pintype "passive"))
      (node (ref "D266") (pin "2") (pinfunction "K_2") (pintype "passive"))
    )
    (net (code "18") (name "Net-(D201-A)") (class "Default")
      (node (ref "D201") (pin "1") (pinfunction "A_1") (pintype "passive"))
      (node (ref "S201") (pin "1") (pinfunction "1_1") (pintype "passive"))
    )
    (net (code "19") (name "Net-(D202-A)") (class "Default")
      (node (ref "D202") (pin "1") (pinfunction "A_1") (pintype "passive"))
      (node (ref "S202") (pin "1") (pinfunction "1_1") (pintype "passive"))
    )
    (net (code "20") (name "Net-(D203-A)") (class "Default")
      (node (ref "D203") (pin "1") (pinfunction "A_1") (pintype "passive"))
      (node (ref "S203") (pin "1") (pinfunction "1_1") (pintype "passive"))
    )
    (net (code "21") (name "Net-(D204-A)") (class "Default")
      (node (ref "D204") (pin "1") (pinfunction "A_1") (pintype "passive"))
      (node (ref "S204") (pin "1") (pinfunction "1_1") (pintype "passive"))
    )
    (net (code "22") (name "Net-(D205-A)") (class "Default")
      (node (ref "D205") (pin "1") (pinfunction "A_1") (pintype "passive"))
      (node (ref "S205") (pin "1") (pinfunction "1_1") (pintype "passive"))
    )
    (net (code "23") (name "Net-(D206-A)") (class "Default")
      (node (ref "D206") (pin "1") (pinfunction "A_1") (pintype "passive"))
      (node (ref "S206") (pin "1") (pinfunction "1_1") (pintype "passive"))
    )
    (net (code "24") (name "Net-(D207-A)") (class "Default")
      (node (ref "D207") (pin "1") (pinfunction "A_1") (pintype "passive"))
      (node (ref "S207") (pin "1") (pinfunction "1_1") (pintype "passive"))
    )
    (net (code "25") (name "Net-(D208-A)") (class "Default")
      (node (ref "D208") (pin "1") (pinfunction "A_1") (pintype "passive"))
      (node (ref "S208") (pin "1") (pinfunction "1_1") (pintype "passive"))
    )
    (net (code "26") (name "Net-(D209-A)") (class "Default")
      (node (ref "D209") (pin "1") (pinfunction "A_1") (pintype "passive"))
      (node (ref "S209") (pin "1") (pinfunction "1_1") (pintype "passive"))
    )
    (net (code "27") (name "Net-(D210-A)") (class "Default")
      (node (ref "D210") (pin "1") (pinfunction "A_1") (pintype "passive"))
      (node (ref "S210") (pin "1") (pinfunction "1_1") (pintype "passive"))
    )
    (net (code "28") (name "Net-(D211-A)") (class "Default")
      (node (ref "D211") (pin "1") (pinfunction "A_1") (pintype "passive"))
      (node (ref "S211") (pin "1") (pinfunction "1_1") (pintype "passive"))
    )
    (net (code "29") (name "Net-(D212-A)") (class "Default")
      (node (ref "D212") (pin "1") (pinfunction "A_1") (pintype "passive"))
      (node (ref "S212") (pin "1") (pinfunction "1_1") (pintype "passive"))
    )
    (net (code "30") (name "Net-(D213-A)") (class "Default")
      (node (ref "D213") (pin "1") (pinfunction "A_1") (pintype "passive"))
      (node (ref "S213") (pin "1") (pinfunction "1_1") (pintype "passive"))
    )
    (net (code "31") (name "Net-(D214-A)") (class "Default")
      (node (ref "D214") (pin "1") (pinfunction "A_1") (pintype "passive"))
      (node (ref "S214") (pin "1") (pinfunction "1_1") (pintype "passive"))
    )
    (net (code "32") (name "Net-(D215-A)") (class "Default")
      (node (ref "D215") (pin "1") (pinfunction "A_1") (pintype "passive"))
      (node (ref "S215") (pin "1") (pinfunction "1_1") (pintype "passive"))
    )
    (net (code "33") (name "Net-(D216-A)") (class "Default")
      (node (ref "D216") (pin "1") (pinfunction "A_1") (pintype "passive"))
      (node (ref "S216") (pin "1") (pinfunction "1_1") (pintype "passive"))
    )
    (net (code "34") (name "Net-(D217-A)") (class "Default")
      (node (ref "D217") (pin "1") (pinfunction "A_1") (pintype "passive"))
      (node (ref "S217") (pin "1") (pinfunction "1_1") (pintype "passive"))
    )
    (net (code "35") (name "Net-(D218-A)") (class "Default")
      (node (ref "D218") (pin "1") (pinfunction "A_1") (pintype "passive"))
      (node (ref "S218") (pin "1") (pinfunction "1_1") (pintype "passive"))
    )
    (net (code "36") (name "Net-(D219-A)") (class "Default")
      (node (ref "D219") (pin "1") (pinfunction "A_1") (pintype "passive"))
      (node (ref "S219") (pin "1") (pinfunction "1_1") (pintype "passive"))
    )
    (net (code "37") (name "Net-(D220-A)") (class "Default")
      (node (ref "D220") (pin "1") (pinfunction "A_1") (pintype "passive"))
      (node (ref "S220") (pin "1") (pinfunction "1_1") (pintype "passive"))
    )
    (net (code "38") (name "Net-(D221-A)") (class "Default")
      (node (ref "D221") (pin "1") (pinfunction "A_1") (pintype "passive"))
      (node (ref "S221") (pin "1") (pinfunction "1_1") (pintype "passive"))
    )
    (net (code "39") (name "Net-(D222-A)") (class "Default")
      (node (ref "D222") (pin "1") (pinfunction "A_1") (pintype "passive"))
      (node (ref "S222") (pin "1") (pinfunction "1_1") (pintype "passive"))
    )
    (net (code "40") (name "Net-(D223-A)") (class "Default")
      (node (ref "D223") (pin "1") (pinfunction "A_1") (pintype "passive"))
      (node (ref "S223") (pin "1") (pinfunction "1_1") (pintype "passive"))
    )
    (net (code "41") (name "Net-(D224-A)") (class "Default")
      (node (ref "D224") (pin "1") (pinfunction "A_1") (pintype "passive"))
      (node (ref "S224") (pin "1") (pinfunction "1_1") (pintype "passive"))
    )
    (net (code "42") (name "Net-(D225-A)") (class "Default")
      (node (ref "D225") (pin "1") (pinfunction "A_1") (pintype "passive"))
      (node (ref "S225") (pin "1") (pinfunction "1_1") (pintype "passive"))
    )
    (net (code "43") (name "Net-(D226-A)") (class "Default")
      (node (ref "D226") (pin "1") (pinfunction "A_1") (pintype "passive"))
      (node (ref "S226") (pin "1") (pinfunction "1_1") (pintype "passive"))
    )
    (net (code "44") (name "Net-(D227-A)") (class "Default")
      (node (ref "D227") (pin "1") (pinfunction "A_1") (pintype "passive"))
      (node (ref "S227") (pin "1") (pinfunction "1_1") (pintype "passive"))
    )
    (net (code "45") (name "Net-(D228-A)") (class "Default")
      (node (ref "D228") (pin "1") (pinfunction "A_1") (pintype "passive"))
      (node (ref "S228") (pin "1") (pinfunction "1_1") (pintype "passive"))
    )
    (net (code "46") (name "Net-(D229-A)") (class "Default")
      (node (ref "D229") (pin "1") (pinfunction "A_1") (pintype "passive"))
      (node (ref "S229") (pin "1") (pinfunction "1_1") (pintype "passive"))
    )
    (net (code "47") (name "Net-(D230-A)") (class "Default")
      (node (ref "D230") (pin "1") (pinfunction "A_1") (pintype "passive"))
      (node (ref "S230") (pin "1") (pinfunction "1_1") (pintype "passive"))
    )
    (net (code "48") (name "Net-(D231-A)") (class "Default")
      (node (ref "D231") (pin "1") (pinfunction "A_1") (pintype "passive"))
      (node (ref "S231") (pin "1") (pinfunction "1_1") (pintype "passive"))
    )
    (net (code "49") (name "Net-(D232-A)") (class "Default")
      (node (ref "D232") (pin "1") (pinfunction "A_1") (pintype "passive"))
      (node (ref "S232") (pin "1") (pinfunction "1_1") (pintype "passive"))
    )
    (net (code "50") (name "Net-(D233-A)") (class "Default")
      (node (ref "D233") (pin "1") (pinfunction "A_1") (pintype "passive"))
      (node (ref "S233") (pin "1") (pinfunction "1_1") (pintype "passive"))
    )
    (net (code "51") (name "Net-(D234-A)") (class "Default")
      (node (ref "D234") (pin "1") (pinfunction "A_1") (pintype "passive"))
      (node (ref "S234") (pin "1") (pinfunction "1_1") (pintype "passive"))
    )
    (net (code "52") (name "Net-(D235-A)") (class "Default")
      (node (ref "D235") (pin "1") (pinfunction "A_1") (pintype "passive"))
      (node (ref "S235") (pin "1") (pinfunction "1_1") (pintype "passive"))
    )
    (net (code "53") (name "Net-(D236-A)") (class "Default")
      (node (ref "D236") (pin "1") (pinfunction "A_1") (pintype "passive"))
      (node (ref "S236") (pin "1") (pinfunction "1_1") (pintype "passive"))
    )
    (net (code "54") (name "Net-(D237-A)") (class "Default")
      (node (ref "D237") (pin "1") (pinfunction "A_1") (pintype "passive"))
      (node (ref "S237") (pin "1") (pinfunction "1_1") (pintype "passive"))
    )
    (net (code "55") (name "Net-(D238-A)") (class "Default")
      (node (ref "D238") (pin "1") (pinfunction "A_1") (pintype "passive"))
      (node (ref "S238") (pin "1") (pinfunction "1_1") (pintype "passive"))
    )
    (net (code "56") (name "Net-(D239-A)") (class "Default")
      (node (ref "D239") (pin "1") (pinfunction "A_1") (pintype "passive"))
      (node (ref "S239") (pin "1") (pinfunction "1_1") (pintype "passive"))
    )
    (net (code "57") (name "Net-(D240-A)") (class "Default")
      (node (ref "D240") (pin "1") (pinfunction "A_1") (pintype "passive"))
      (node (ref "S240") (pin "1") (pinfunction "1_1") (pintype "passive"))
    )
    (net (code "58") (name "Net-(D241-A)") (class "Default")
      (node (ref "D241") (pin "1") (pinfunction "A_1") (pintype "passive"))
      (node (ref "S241") (pin "1") (pinfunction "1_1") (pintype "passive"))
    )
    (net (code "59") (name "Net-(D242-A)") (class "Default")
      (node (ref "D242") (pin "1") (pinfunction "A_1") (pintype "passive"))
      (node (ref "S242") (pin "1") (pinfunction "1_1") (pintype "passive"))
    )
    (net (code "60") (name "Net-(D243-A)") (class "Default")
      (node (ref "D243") (pin "1") (pinfunction "A_1") (pintype "passive"))
      (node (ref "S243") (pin "1") (pinfunction "1_1") (pintype "passive"))
    )
    (net (code "61") (name "Net-(D244-A)") (class "Default")
      (node (ref "D244") (pin "1") (pinfunction "A_1") (pintype "passive"))
      (node (ref "S244") (pin "1") (pinfunction "1_1") (pintype "passive"))
    )
    (net (code "62") (name "Net-(D245-A)") (class "Default")
      (node (ref "D245") (pin "1") (pinfunction "A_1") (pintype "passive"))
      (node (ref "S245") (pin "1") (pinfunction "1_1") (pintype "passive"))
    )
    (net (code "63") (name "Net-(D246-A)") (class "Default")
      (node (ref "D246") (pin "1") (pinfunction "A_1") (pintype "passive"))
      (node (ref "S246") (pin "1") (pinfunction "1_1") (pintype "passive"))
    )
    (net (code "64") (name "Net-(D247-A)") (class "Default")
      (node (ref "D247") (pin "1") (pinfunction "A_1") (pintype "passive"))
      (node (ref "S247") (pin "1") (pinfunction "1_1") (pintype "passive"))
    )
    (net (code "65") (name "Net-(D248-A)") (class "Default")
      (node (ref "D248") (pin "1") (pinfunction "A_1") (pintype "passive"))
      (node (ref "S248") (pin "1") (pinfunction "1_1") (pintype "passive"))
    )
    (net (code "66") (name "Net-(D249-A)") (class "Default")
      (node (ref "D249") (pin "1") (pinfunction "A_1") (pintype "passive"))
      (node (ref "S249") (pin "1") (pinfunction "1_1") (pintype "passive"))
    )
    (net (code "67") (name "Net-(D250-A)") (class "Default")
      (node (ref "D250") (pin "1") (pinfunction "A_1") (pintype "passive"))
      (node (ref "S250") (pin "1") (pinfunction "1_1") (pintype "passive"))
    )
    (net (code "68") (name "Net-(D251-A)") (class "Default")
      (node (ref "D251") (pin "1") (pinfunction "A_1") (pintype "passive"))
      (node (ref "S251") (pin "1") (pinfunction "1_1") (pintype "passive"))
    )
    (net (code "69") (name "Net-(D252-A)") (class "Default")
      (node (ref "D252") (pin "1") (pinfunction "A_1") (pintype "passive"))
      (node (ref "S252") (pin "1") (pinfunction "1_1") (pintype "passive"))
    )
    (net (code "70") (name "Net-(D253-A)") (class "Default")
      (node (ref "D253") (pin "1") (pinfunction "A_1") (pintype "passive"))
      (node (ref "S253") (pin "1") (pinfunction "1_1") (pintype "passive"))
    )
    (net (code "71") (name "Net-(D254-A)") (class "Default")
      (node (ref "D254") (pin "1") (pinfunction "A_1") (pintype "passive"))
      (node (ref "S254") (pin "1") (pinfunction "1_1") (pintype "passive"))
    )
    (net (code "72") (name "Net-(D256-A)") (class "Default")
      (node (ref "D256") (pin "1") (pinfunction "A_1") (pintype "passive"))
      (node (ref "S256") (pin "1") (pinfunction "1_1") (pintype "passive"))
    )
    (net (code "73") (name "Net-(D257-A)") (class "Default")
      (node (ref "D257") (pin "1") (pinfunction "A_1") (pintype "passive"))
      (node (ref "S257") (pin "1") (pinfunction "1_1") (pintype "passive"))
    )
    (net (code "74") (name "Net-(D258-A)") (class "Default")
      (node (ref "D258") (pin "1") (pinfunction "A_1") (pintype "passive"))
      (node (ref "S258") (pin "1") (pinfunction "1_1") (pintype "passive"))
    )
    (net (code "75") (name "Net-(D259-A)") (class "Default")
      (node (ref "D259") (pin "1") (pinfunction "A_1") (pintype "passive"))
      (node (ref "S259") (pin "1") (pinfunction "1_1") (pintype "passive"))
    )
    (net (code "76") (name "Net-(D260-A)") (class "Default")
      (node (ref "D260") (pin "1") (pinfunction "A_1") (pintype "passive"))
      (node (ref "S260") (pin "1") (pinfunction "1_1") (pintype "passive"))
    )
    (net (code "77") (name "Net-(D261-A)") (class "Default")
      (node (ref "D261") (pin "1") (pinfunction "A_1") (pintype "passive"))
      (node (ref "S261") (pin "1") (pinfunction "1_1") (pintype "passive"))
    )
    (net (code "78") (name "Net-(D262-A)") (class "Default")
      (node (ref "D262") (pin "1") (pinfunction "A_1") (pintype "passive"))
      (node (ref "S262") (pin "1") (pinfunction "1_1") (pintype "passive"))
    )
    (net (code "79") (name "Net-(D263-A)") (class "Default")
      (node (ref "D263") (pin "1") (pinfunction "A_1") (pintype "passive"))
      (node (ref "S263") (pin "1") (pinfunction "1_1") (pintype "passive"))
    )
    (net (code "80") (name "Net-(D264-A)") (class "Default")
      (node (ref "D264") (pin "1") (pinfunction "A_1") (pintype "passive"))
      (node (ref "S264") (pin "1") (pinfunction "1_1") (pintype "passive"))
    )
    (net (code "81") (name "Net-(D265-A)") (class "Default")
      (node (ref "D265") (pin "1") (pinfunction "A_1") (pintype "passive"))
      (node (ref "S265") (pin "1") (pinfunction "1_1") (pintype "passive"))
    )
    (net (code "82") (name "Net-(D266-A)") (class "Default")
      (node (ref "D266") (pin "1") (pinfunction "A_1") (pintype "passive"))
      (node (ref "S266") (pin "1") (pinfunction "1_1") (pintype "passive"))
    )
    (net (code "83") (name "Net-(D269-A)") (class "Default")
      (node (ref "D269") (pin "1") (pinfunction "A_1") (pintype "passive"))
      (node (ref "S269") (pin "1") (pinfunction "1_1") (pintype "passive"))
    )
  )
)
